# PSU_Manager.net
KiCad netlist of a schematic drawn in Altium Designer
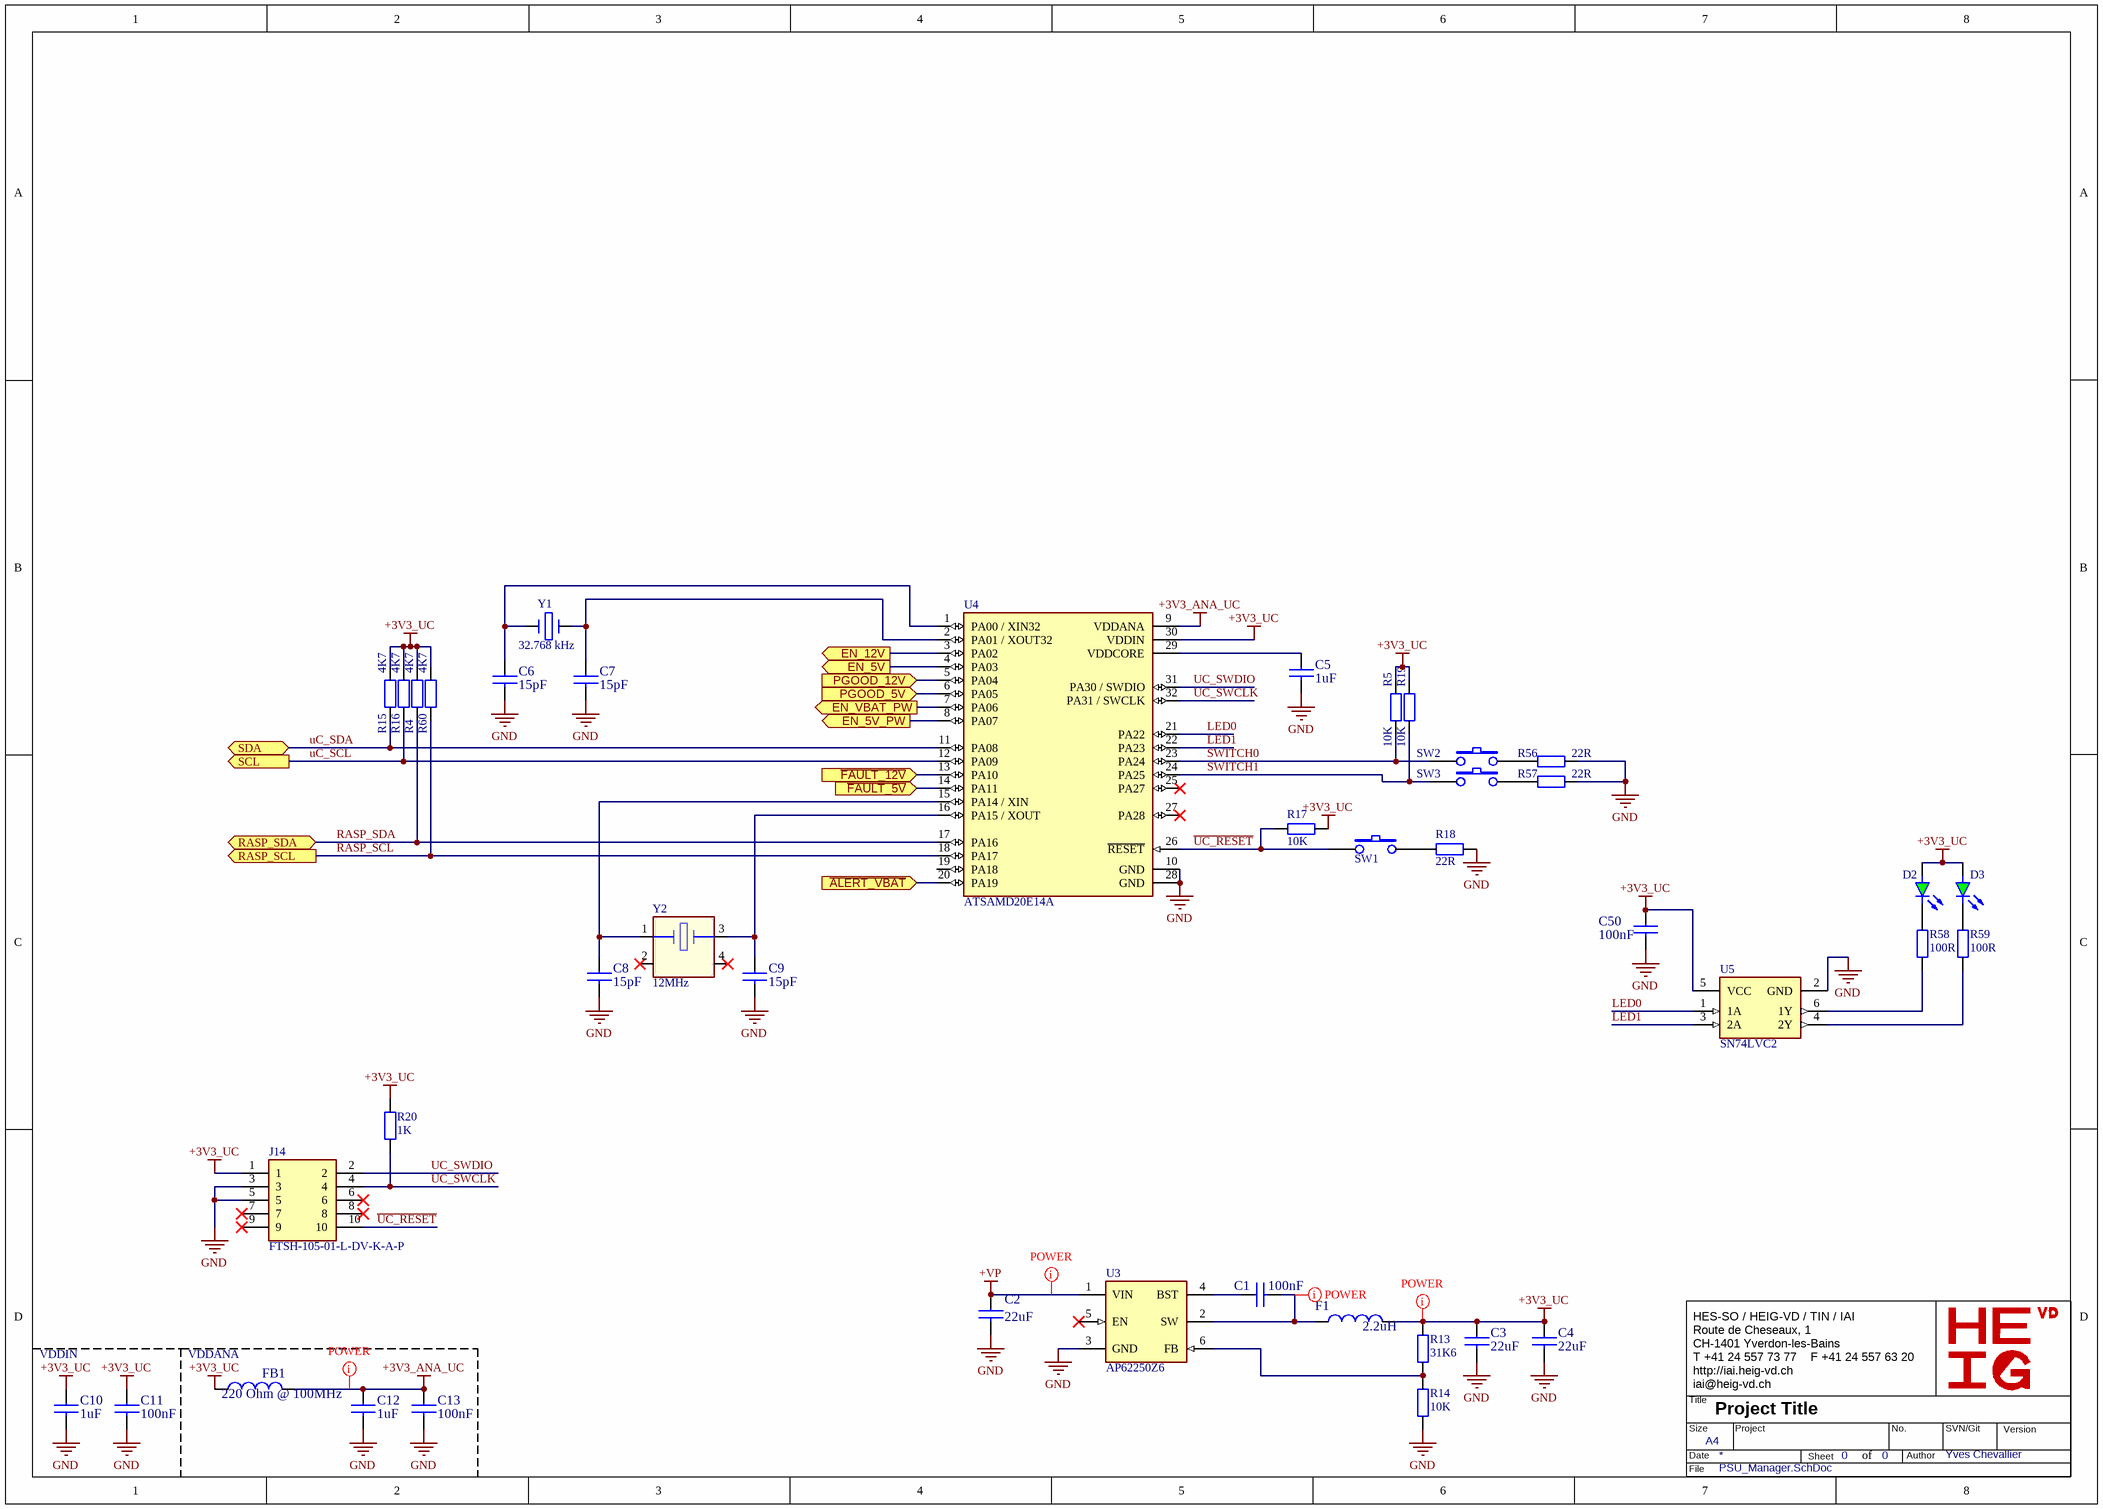
[diagram p0: PSU_Manager.SchDoc]

(export (version "E")
  (design (tool "Eeschema 10.0.6"))
  (components
    (comp (ref "C1")
      (value "100nF")
      (footprint "SM/C_0603")
      (description "CAP CER 0.1UF 16V X7R 0603")
      (fields (field (name "MANUFACTURER") "Samsung") (field (name "TOLERANCE") "10%"))
      (libsource (lib "Battery_PSU") (part "CAP CER 0.1UF 16V X7R 0603"))
    )
    (comp (ref "C2")
      (value "22uF")
      (footprint "SM/C_1210")
      (description "CAP CER 22UF 25V X5R 1210")
      (fields (field (name "MANUFACTURER") "Samsung") (field (name "VOLTAGE") "25V"))
      (libsource (lib "Battery_PSU") (part "CAP CER 22UF 25V X5R 1210"))
    )
    (comp (ref "C3")
      (value "22uF")
      (footprint "SM/C_1210")
      (description "CAP CER 22UF 25V X5R 1210")
      (fields (field (name "MANUFACTURER") "Samsung") (field (name "VOLTAGE") "25V"))
      (libsource (lib "Battery_PSU") (part "CAP CER 22UF 25V X5R 1210"))
    )
    (comp (ref "C4")
      (value "22uF")
      (footprint "SM/C_1210")
      (description "CAP CER 22UF 25V X5R 1210")
      (fields (field (name "MANUFACTURER") "Samsung") (field (name "VOLTAGE") "25V"))
      (libsource (lib "Battery_PSU") (part "CAP CER 22UF 25V X5R 1210"))
    )
    (comp (ref "C5")
      (value "1uF")
      (footprint "SM/C_0603")
      (description "CAP CER 1UF 10V X7R 0603")
      (fields (field (name "MANUFACTURER") "Samsung") (field (name "TOLERANCE") "10%"))
      (libsource (lib "Battery_PSU") (part "CAP CER 1UF 10V X7R 0603"))
    )
    (comp (ref "C6")
      (value "15pF")
      (footprint "SM/C_0603")
      (description "CAP CER 15PF 50V C0G/NP0 0603")
      (fields (field (name "MANUFACTURER") "AVX") (field (name "TOLERANCE") "5%"))
      (libsource (lib "Battery_PSU") (part "CAP CER 15PF 50V C0G/NP0 0603"))
    )
    (comp (ref "C7")
      (value "15pF")
      (footprint "SM/C_0603")
      (description "CAP CER 15PF 50V C0G/NP0 0603")
      (fields (field (name "MANUFACTURER") "AVX") (field (name "TOLERANCE") "5%"))
      (libsource (lib "Battery_PSU") (part "CAP CER 15PF 50V C0G/NP0 0603"))
    )
    (comp (ref "C8")
      (value "15pF")
      (footprint "SM/C_0603")
      (description "CAP CER 15PF 50V C0G/NP0 0603")
      (fields (field (name "MANUFACTURER") "AVX") (field (name "TOLERANCE") "5%"))
      (libsource (lib "Battery_PSU") (part "CAP CER 15PF 50V C0G/NP0 0603"))
    )
    (comp (ref "C9")
      (value "15pF")
      (footprint "SM/C_0603")
      (description "CAP CER 15PF 50V C0G/NP0 0603")
      (fields (field (name "MANUFACTURER") "AVX") (field (name "TOLERANCE") "5%"))
      (libsource (lib "Battery_PSU") (part "CAP CER 15PF 50V C0G/NP0 0603"))
    )
    (comp (ref "C10")
      (value "1uF")
      (footprint "SM/C_0603")
      (description "CAP CER 1UF 10V X7R 0603")
      (fields (field (name "MANUFACTURER") "Samsung") (field (name "TOLERANCE") "10%"))
      (libsource (lib "Battery_PSU") (part "CAP CER 1UF 10V X7R 0603"))
    )
    (comp (ref "C11")
      (value "100nF")
      (footprint "SM/C_0603")
      (description "CAP CER 0.1UF 16V X7R 0603")
      (fields (field (name "MANUFACTURER") "Samsung") (field (name "TOLERANCE") "10%"))
      (libsource (lib "Battery_PSU") (part "CAP CER 0.1UF 16V X7R 0603"))
    )
    (comp (ref "C12")
      (value "1uF")
      (footprint "SM/C_0603")
      (description "CAP CER 1UF 10V X7R 0603")
      (fields (field (name "MANUFACTURER") "Samsung") (field (name "TOLERANCE") "10%"))
      (libsource (lib "Battery_PSU") (part "CAP CER 1UF 10V X7R 0603"))
    )
    (comp (ref "C13")
      (value "100nF")
      (footprint "SM/C_0603")
      (description "CAP CER 0.1UF 16V X7R 0603")
      (fields (field (name "MANUFACTURER") "Samsung") (field (name "TOLERANCE") "10%"))
      (libsource (lib "Battery_PSU") (part "CAP CER 0.1UF 16V X7R 0603"))
    )
    (comp (ref "C50")
      (value "100nF")
      (footprint "SM/C_0603")
      (description "CAP CER 0.1UF 16V X7R 0603")
      (fields (field (name "MANUFACTURER") "Samsung") (field (name "TOLERANCE") "10%"))
      (libsource (lib "Battery_PSU") (part "CAP CER 0.1UF 16V X7R 0603"))
    )
    (comp (ref "D2")
      (value "Green")
      (footprint "WL-SMCW_0603 - Green")
      (description "LED GREEN CLEAR 0603 SMD")
      (fields (field (name "MANUFACTURER") "Würth Elektronik"))
      (libsource (lib "Battery_PSU") (part "LED GREEN CLEAR 0603 SMD"))
    )
    (comp (ref "D3")
      (value "Green")
      (footprint "WL-SMCW_0603 - Green")
      (description "LED GREEN CLEAR 0603 SMD")
      (fields (field (name "MANUFACTURER") "Würth Elektronik"))
      (libsource (lib "Battery_PSU") (part "LED GREEN CLEAR 0603 SMD"))
    )
    (comp (ref "F1")
      (value "2.2uH")
      (description "FIXED IND 2.2UH 4.7A 28.6MOHM SMD")
      (fields (field (name "MANUFACTURER") "TDK"))
      (libsource (lib "Battery_PSU") (part "FIXED IND 2.2UH 4.7A 28.6MOHM SMD"))
    )
    (comp (ref "FB1")
      (value "220 Ohm @ 100MHz")
      (description "FERRITE BEAD 220 OHM 0603 1LN")
      (fields (field (name "MANUFACTURER") "Murata"))
      (libsource (lib "Battery_PSU") (part "FERRITE 220 Ohms 0603"))
    )
    (comp (ref "J14")
      (value "FTSH-105-01-L-DV-K-A-P")
      (footprint "FTSH-105-XX-YYY-DV-K-A-P-TR")
      (description "CONN HEADER SMD 10POS 1.27MM")
      (fields (field (name "MANUFACTURER") "Samtec"))
      (libsource (lib "Battery_PSU") (part "CONN HEADER SMD 10POS 1.27MM"))
    )
    (comp (ref "R4")
      (value "4K7")
      (footprint "SM/R_0603")
      (description "RES SMD 4.7K OHM 1% 1/10W 0603")
      (fields (field (name "MANUFACTURER") "Yageo") (field (name "POWER") "100mW"))
      (libsource (lib "Battery_PSU") (part "RES SMD 4.7K OHM 1% 1/10W 0603"))
    )
    (comp (ref "R5")
      (value "10K")
      (footprint "SM/R_0603")
      (description "Résistance 0603 100mW 1% 10K")
      (fields (field (name "MANUFACTURER") "Yageo") (field (name "POWER") "100mW"))
      (libsource (lib "Battery_PSU") (part "RES SMD 10K OHM 1% 1/10W 0603"))
    )
    (comp (ref "R13")
      (value "31K6")
      (footprint "SM/R_0603")
      (description "RES SMD 31.6K OHM 1% 1/10W 0603")
      (fields (field (name "MANUFACTURER") "Yageo") (field (name "POWER") "100mW"))
      (libsource (lib "Battery_PSU") (part "RES SMD 31.6K OHM 1% 1/10W 0603"))
    )
    (comp (ref "R14")
      (value "10K")
      (footprint "SM/R_0603")
      (description "Résistance 0603 100mW 1% 10K")
      (fields (field (name "MANUFACTURER") "Yageo") (field (name "POWER") "100mW"))
      (libsource (lib "Battery_PSU") (part "RES SMD 10K OHM 1% 1/10W 0603"))
    )
    (comp (ref "R15")
      (value "4K7")
      (footprint "SM/R_0603")
      (description "RES SMD 4.7K OHM 1% 1/10W 0603")
      (fields (field (name "MANUFACTURER") "Yageo") (field (name "POWER") "100mW"))
      (libsource (lib "Battery_PSU") (part "RES SMD 4.7K OHM 1% 1/10W 0603"))
    )
    (comp (ref "R16")
      (value "4K7")
      (footprint "SM/R_0603")
      (description "RES SMD 4.7K OHM 1% 1/10W 0603")
      (fields (field (name "MANUFACTURER") "Yageo") (field (name "POWER") "100mW"))
      (libsource (lib "Battery_PSU") (part "RES SMD 4.7K OHM 1% 1/10W 0603"))
    )
    (comp (ref "R17")
      (value "10K")
      (footprint "SM/R_0603")
      (description "Résistance 0603 100mW 1% 10K")
      (fields (field (name "MANUFACTURER") "Yageo") (field (name "POWER") "100mW"))
      (libsource (lib "Battery_PSU") (part "RES SMD 10K OHM 1% 1/10W 0603"))
    )
    (comp (ref "R18")
      (value "22R")
      (footprint "SM/R_0603")
      (description "RES SMD 22 OHM 1% 1/10W 0603")
      (fields (field (name "MANUFACTURER") "Yageo") (field (name "POWER") "100mW"))
      (libsource (lib "Battery_PSU") (part "RES SMD 22 OHM 1% 1/10W 0603"))
    )
    (comp (ref "R19")
      (value "10K")
      (footprint "SM/R_0603")
      (description "Résistance 0603 100mW 1% 10K")
      (fields (field (name "MANUFACTURER") "Yageo") (field (name "POWER") "100mW"))
      (libsource (lib "Battery_PSU") (part "RES SMD 10K OHM 1% 1/10W 0603"))
    )
    (comp (ref "R20")
      (value "1K")
      (footprint "SM/R_0603")
      (description "RES SMD 1K OHM 1% 1/10W 0603")
      (fields (field (name "MANUFACTURER") "Yageo") (field (name "POWER") "100mW"))
      (libsource (lib "Battery_PSU") (part "RES SMD 1K OHM 1% 1/10W 0603"))
    )
    (comp (ref "R56")
      (value "22R")
      (footprint "SM/R_0603")
      (description "RES SMD 22 OHM 1% 1/10W 0603")
      (fields (field (name "MANUFACTURER") "Yageo") (field (name "POWER") "100mW"))
      (libsource (lib "Battery_PSU") (part "RES SMD 22 OHM 1% 1/10W 0603"))
    )
    (comp (ref "R57")
      (value "22R")
      (footprint "SM/R_0603")
      (description "RES SMD 22 OHM 1% 1/10W 0603")
      (fields (field (name "MANUFACTURER") "Yageo") (field (name "POWER") "100mW"))
      (libsource (lib "Battery_PSU") (part "RES SMD 22 OHM 1% 1/10W 0603"))
    )
    (comp (ref "R58")
      (value "100R")
      (footprint "SM/R_0603")
      (description "RES 100 OHM 1% 1/10W 0603")
      (fields (field (name "MANUFACTURER") "Yageo") (field (name "POWER") "100mW"))
      (libsource (lib "Battery_PSU") (part "RES 100 OHM 1% 1/10W 0603"))
    )
    (comp (ref "R59")
      (value "100R")
      (footprint "SM/R_0603")
      (description "RES 100 OHM 1% 1/10W 0603")
      (fields (field (name "MANUFACTURER") "Yageo") (field (name "POWER") "100mW"))
      (libsource (lib "Battery_PSU") (part "RES 100 OHM 1% 1/10W 0603"))
    )
    (comp (ref "R60")
      (value "4K7")
      (footprint "SM/R_0603")
      (description "RES SMD 4.7K OHM 1% 1/10W 0603")
      (fields (field (name "MANUFACTURER") "Yageo") (field (name "POWER") "100mW"))
      (libsource (lib "Battery_PSU") (part "RES SMD 4.7K OHM 1% 1/10W 0603"))
    )
    (comp (ref "SW1")
      (value "SW_PUSHBUTTON")
      (footprint "Omron_SWITCH_B3U-1000P")
      (description "Tactile Switch SPST-NO Top Actuated SMD")
      (fields (field (name "MANUFACTURER") "Omron Electronics") (field (name "VOLTAGE") "12V"))
      (libsource (lib "Battery_PSU") (part "SWITCH TACTILE SPST-NO 0.05A 12V"))
    )
    (comp (ref "SW2")
      (value "SW_PUSHBUTTON")
      (footprint "Omron_SWITCH_B3U-1000P")
      (description "Tactile Switch SPST-NO Top Actuated SMD")
      (fields (field (name "MANUFACTURER") "Omron Electronics") (field (name "VOLTAGE") "12V"))
      (libsource (lib "Battery_PSU") (part "SWITCH TACTILE SPST-NO 0.05A 12V"))
    )
    (comp (ref "SW3")
      (value "SW_PUSHBUTTON")
      (footprint "Omron_SWITCH_B3U-1000P")
      (description "Tactile Switch SPST-NO Top Actuated SMD")
      (fields (field (name "MANUFACTURER") "Omron Electronics") (field (name "VOLTAGE") "12V"))
      (libsource (lib "Battery_PSU") (part "SWITCH TACTILE SPST-NO 0.05A 12V"))
    )
    (comp (ref "U3")
      (value "AP62250Z6")
      (footprint "SOT563-6")
      (description "DCDC CONV BUCK 3A SOT563")
      (fields (field (name "MANUFACTURER") "Diodes Incorporated"))
      (libsource (lib "Battery_PSU") (part "AP62250Z6-7"))
    )
    (comp (ref "U4")
      (value "ATSAMD20E14A")
      (footprint "VFQFN-32_(32-Lead LFCSP_VQ)")
      (description "IC MCU 32BIT 16KB FLASH 32QFN")
      (fields (field (name "MANUFACTURER") "Microchip"))
      (libsource (lib "Battery_PSU") (part "IC MCU 32BIT 16KB FLASH 32QFN"))
    )
    (comp (ref "U5")
      (value "SN74LVC2")
      (footprint "SOT23-6")
      (description "IC INVERTER 2CH 2-INP SOT23-6")
      (fields (field (name "MANUFACTURER") "Texas Instruments"))
      (libsource (lib "Battery_PSU") (part "SN74LVC2GU04DBVR"))
    )
    (comp (ref "Y1")
      (value "32.768 kHz")
      (footprint "ABRACON_CRYSTAL_ABS06 SERIES")
      (description "CRYSTAL 32.7680KHZ 12.5PF SMD")
      (fields (field (name "MANUFACTURER") "Abracon LLC"))
      (libsource (lib "Battery_PSU") (part "CRYSTAL 32.7680KHZ 12.5PF SMD"))
    )
    (comp (ref "Y2")
      (value "12MHz")
      (footprint "ABRACON_CRYSTAL_ABM10AIG SERIES")
      (description "CRYSTAL 12.0000MHZ 10PF SMD")
      (fields (field (name "MANUFACTURER") "Abracon LLC"))
      (libsource (lib "Battery_PSU") (part "CRYSTAL 12.0000MHZ 10PF SMD"))
    )
  )
  (nets
    (net (code "1") (name "+3V3_ANA_UC") (class "Default")
      (node (ref "C12") (pin "1") (pinfunction "1_1") (pintype "passive"))
      (node (ref "C13") (pin "1") (pinfunction "1_1") (pintype "passive"))
      (node (ref "FB1") (pin "2") (pinfunction "2_2") (pintype "passive"))
      (node (ref "U4") (pin "9") (pinfunction "VDDANA_9") (pintype "power_in"))
    )
    (net (code "2") (name "+3V3_UC") (class "Default")
      (node (ref "C10") (pin "1") (pinfunction "1_1") (pintype "passive"))
      (node (ref "C11") (pin "1") (pinfunction "1_1") (pintype "passive"))
      (node (ref "C3") (pin "1") (pinfunction "1_1") (pintype "passive"))
      (node (ref "C4") (pin "1") (pinfunction "1_1") (pintype "passive"))
      (node (ref "C50") (pin "1") (pinfunction "1_1") (pintype "passive"))
      (node (ref "D2") (pin "2") (pinfunction "A_2") (pintype "passive"))
      (node (ref "D3") (pin "2") (pinfunction "A_2") (pintype "passive"))
      (node (ref "F1") (pin "2") (pinfunction "2_2") (pintype "passive"))
      (node (ref "FB1") (pin "1") (pinfunction "1_1") (pintype "passive"))
      (node (ref "J14") (pin "1") (pinfunction "1_1") (pintype "passive"))
      (node (ref "R13") (pin "1") (pinfunction "1_1") (pintype "passive"))
      (node (ref "R15") (pin "1") (pinfunction "1_1") (pintype "passive"))
      (node (ref "R16") (pin "1") (pinfunction "1_1") (pintype "passive"))
      (node (ref "R17") (pin "2") (pinfunction "2_2") (pintype "passive"))
      (node (ref "R19") (pin "2") (pinfunction "2_2") (pintype "passive"))
      (node (ref "R20") (pin "1") (pinfunction "1_1") (pintype "passive"))
      (node (ref "R4") (pin "1") (pinfunction "1_1") (pintype "passive"))
      (node (ref "R5") (pin "2") (pinfunction "2_2") (pintype "passive"))
      (node (ref "R60") (pin "1") (pinfunction "1_1") (pintype "passive"))
      (node (ref "U4") (pin "30") (pinfunction "VDDIN_30") (pintype "power_in"))
      (node (ref "U5") (pin "5") (pinfunction "VCC_5") (pintype "power_in"))
    )
    (net (code "3") (name "+VP") (class "Default")
      (node (ref "C2") (pin "1") (pinfunction "1_1") (pintype "passive"))
      (node (ref "U3") (pin "1") (pinfunction "VIN_1") (pintype "power_in"))
    )
    (net (code "4") (name "/ALERT_VBAT") (class "Default")
      (node (ref "U4") (pin "20") (pinfunction "PA19_20") (pintype "bidirectional"))
    )
    (net (code "5") (name "/EN_5V") (class "Default")
      (node (ref "U4") (pin "4") (pinfunction "PA03_4") (pintype "bidirectional"))
    )
    (net (code "6") (name "/EN_5V_PW") (class "Default")
      (node (ref "U4") (pin "8") (pinfunction "PA07_8") (pintype "bidirectional"))
    )
    (net (code "7") (name "/EN_12V") (class "Default")
      (node (ref "U4") (pin "3") (pinfunction "PA02_3") (pintype "bidirectional"))
    )
    (net (code "8") (name "/EN_VBAT_PW") (class "Default")
      (node (ref "U4") (pin "7") (pinfunction "PA06_7") (pintype "bidirectional"))
    )
    (net (code "9") (name "/FAULT_5V") (class "Default")
      (node (ref "U4") (pin "14") (pinfunction "PA11_14") (pintype "bidirectional"))
    )
    (net (code "10") (name "/FAULT_12V") (class "Default")
      (node (ref "U4") (pin "13") (pinfunction "PA10_13") (pintype "bidirectional"))
    )
    (net (code "11") (name "/LED0") (class "Default")
      (node (ref "U4") (pin "21") (pinfunction "PA22_21") (pintype "bidirectional"))
      (node (ref "U5") (pin "1") (pinfunction "1A_1") (pintype "input"))
    )
    (net (code "12") (name "/LED1") (class "Default")
      (node (ref "U4") (pin "22") (pinfunction "PA23_22") (pintype "bidirectional"))
      (node (ref "U5") (pin "3") (pinfunction "2A_3") (pintype "input"))
    )
    (net (code "13") (name "/PGOOD_5V") (class "Default")
      (node (ref "U4") (pin "6") (pinfunction "PA05_6") (pintype "bidirectional"))
    )
    (net (code "14") (name "/PGOOD_12V") (class "Default")
      (node (ref "U4") (pin "5") (pinfunction "PA04_5") (pintype "bidirectional"))
    )
    (net (code "15") (name "/RASP_SCL") (class "Default")
      (node (ref "R60") (pin "2") (pinfunction "2_2") (pintype "passive"))
      (node (ref "U4") (pin "18") (pinfunction "PA17_18") (pintype "bidirectional"))
    )
    (net (code "16") (name "/RASP_SDA") (class "Default")
      (node (ref "R4") (pin "2") (pinfunction "2_2") (pintype "passive"))
      (node (ref "U4") (pin "17") (pinfunction "PA16_17") (pintype "bidirectional"))
    )
    (net (code "17") (name "/SWITCH0") (class "Default")
      (node (ref "R5") (pin "1") (pinfunction "1_1") (pintype "passive"))
      (node (ref "SW2") (pin "1") (pinfunction "1_1") (pintype "passive"))
      (node (ref "U4") (pin "23") (pinfunction "PA24_23") (pintype "bidirectional"))
    )
    (net (code "18") (name "/SWITCH1") (class "Default")
      (node (ref "R19") (pin "1") (pinfunction "1_1") (pintype "passive"))
      (node (ref "SW3") (pin "1") (pinfunction "1_1") (pintype "passive"))
      (node (ref "U4") (pin "24") (pinfunction "PA25_24") (pintype "bidirectional"))
    )
    (net (code "19") (name "/UC_RESET") (class "Default")
      (node (ref "J14") (pin "10") (pinfunction "10_10") (pintype "passive"))
      (node (ref "R17") (pin "1") (pinfunction "1_1") (pintype "passive"))
      (node (ref "SW1") (pin "1") (pinfunction "1_1") (pintype "passive"))
      (node (ref "U4") (pin "26") (pinfunction "RESET_26") (pintype "input"))
    )
    (net (code "20") (name "/UC_SWCLK") (class "Default")
      (node (ref "J14") (pin "4") (pinfunction "4_4") (pintype "passive"))
      (node (ref "R20") (pin "2") (pinfunction "2_2") (pintype "passive"))
      (node (ref "U4") (pin "32") (pinfunction "PA31_/_SWCLK_32") (pintype "bidirectional"))
    )
    (net (code "21") (name "/UC_SWDIO") (class "Default")
      (node (ref "J14") (pin "2") (pinfunction "2_2") (pintype "passive"))
      (node (ref "U4") (pin "31") (pinfunction "PA30_/_SWDIO_31") (pintype "bidirectional"))
    )
    (net (code "22") (name "/uC_SCL") (class "Default")
      (node (ref "R16") (pin "2") (pinfunction "2_2") (pintype "passive"))
      (node (ref "U4") (pin "12") (pinfunction "PA09_12") (pintype "bidirectional"))
    )
    (net (code "23") (name "/uC_SDA") (class "Default")
      (node (ref "R15") (pin "2") (pinfunction "2_2") (pintype "passive"))
      (node (ref "U4") (pin "11") (pinfunction "PA08_11") (pintype "bidirectional"))
    )
    (net (code "24") (name "GND") (class "Default")
      (node (ref "C10") (pin "2") (pinfunction "2_2") (pintype "passive"))
      (node (ref "C11") (pin "2") (pinfunction "2_2") (pintype "passive"))
      (node (ref "C12") (pin "2") (pinfunction "2_2") (pintype "passive"))
      (node (ref "C13") (pin "2") (pinfunction "2_2") (pintype "passive"))
      (node (ref "C2") (pin "2") (pinfunction "2_2") (pintype "passive"))
      (node (ref "C3") (pin "2") (pinfunction "2_2") (pintype "passive"))
      (node (ref "C4") (pin "2") (pinfunction "2_2") (pintype "passive"))
      (node (ref "C5") (pin "2") (pinfunction "2_2") (pintype "passive"))
      (node (ref "C50") (pin "2") (pinfunction "2_2") (pintype "passive"))
      (node (ref "C6") (pin "2") (pinfunction "2_2") (pintype "passive"))
      (node (ref "C7") (pin "2") (pinfunction "2_2") (pintype "passive"))
      (node (ref "C8") (pin "2") (pinfunction "2_2") (pintype "passive"))
      (node (ref "C9") (pin "2") (pinfunction "2_2") (pintype "passive"))
      (node (ref "J14") (pin "3") (pinfunction "3_3") (pintype "passive"))
      (node (ref "J14") (pin "5") (pinfunction "5_5") (pintype "passive"))
      (node (ref "R14") (pin "2") (pinfunction "2_2") (pintype "passive"))
      (node (ref "R18") (pin "2") (pinfunction "2_2") (pintype "passive"))
      (node (ref "R56") (pin "2") (pinfunction "2_2") (pintype "passive"))
      (node (ref "R57") (pin "2") (pinfunction "2_2") (pintype "passive"))
      (node (ref "U3") (pin "3") (pinfunction "GND_3") (pintype "power_in"))
      (node (ref "U4") (pin "10") (pinfunction "GND_10") (pintype "power_in"))
      (node (ref "U4") (pin "28") (pinfunction "GND_28") (pintype "power_in"))
      (node (ref "U5") (pin "2") (pinfunction "GND_2") (pintype "power_in"))
    )
    (net (code "25") (name "Net-(D2-C)") (class "Default")
      (node (ref "D2") (pin "1") (pinfunction "C_1") (pintype "passive"))
      (node (ref "R58") (pin "1") (pinfunction "1_1") (pintype "passive"))
    )
    (net (code "26") (name "Net-(D3-C)") (class "Default")
      (node (ref "D3") (pin "1") (pinfunction "C_1") (pintype "passive"))
      (node (ref "R59") (pin "1") (pinfunction "1_1") (pintype "passive"))
    )
    (net (code "27") (name "Net-(R18-Pad1)") (class "Default")
      (node (ref "R18") (pin "1") (pinfunction "1_1") (pintype "passive"))
      (node (ref "SW1") (pin "2") (pinfunction "2_2") (pintype "passive"))
    )
    (net (code "28") (name "Net-(R56-Pad1)") (class "Default")
      (node (ref "R56") (pin "1") (pinfunction "1_1") (pintype "passive"))
      (node (ref "SW2") (pin "2") (pinfunction "2_2") (pintype "passive"))
    )
    (net (code "29") (name "Net-(R57-Pad1)") (class "Default")
      (node (ref "R57") (pin "1") (pinfunction "1_1") (pintype "passive"))
      (node (ref "SW3") (pin "2") (pinfunction "2_2") (pintype "passive"))
    )
    (net (code "30") (name "Net-(U3-BST)") (class "Default")
      (node (ref "C1") (pin "1") (pinfunction "1_1") (pintype "passive"))
      (node (ref "U3") (pin "4") (pinfunction "BST_4") (pintype "passive"))
    )
    (net (code "31") (name "Net-(U3-FB)") (class "Default")
      (node (ref "R13") (pin "2") (pinfunction "2_2") (pintype "passive"))
      (node (ref "R14") (pin "1") (pinfunction "1_1") (pintype "passive"))
      (node (ref "U3") (pin "6") (pinfunction "FB_6") (pintype "input"))
    )
    (net (code "32") (name "Net-(U3-SW)") (class "Default")
      (node (ref "C1") (pin "2") (pinfunction "2_2") (pintype "passive"))
      (node (ref "F1") (pin "1") (pinfunction "1_1") (pintype "passive"))
      (node (ref "U3") (pin "2") (pinfunction "SW_2") (pintype "power_in"))
    )
    (net (code "33") (name "Net-(U4-PA00_{slash}_XIN32)") (class "Default")
      (node (ref "C6") (pin "1") (pinfunction "1_1") (pintype "passive"))
      (node (ref "U4") (pin "1") (pinfunction "PA00_/_XIN32_1") (pintype "bidirectional"))
      (node (ref "Y1") (pin "1") (pintype "passive"))
    )
    (net (code "34") (name "Net-(U4-PA01_{slash}_XOUT32)") (class "Default")
      (node (ref "C7") (pin "1") (pinfunction "1_1") (pintype "passive"))
      (node (ref "U4") (pin "2") (pinfunction "PA01_/_XOUT32_2") (pintype "bidirectional"))
      (node (ref "Y1") (pin "2") (pintype "passive"))
    )
    (net (code "35") (name "Net-(U4-PA14_{slash}_XIN)") (class "Default")
      (node (ref "C8") (pin "1") (pinfunction "1_1") (pintype "passive"))
      (node (ref "U4") (pin "15") (pinfunction "PA14_/_XIN_15") (pintype "bidirectional"))
      (node (ref "Y2") (pin "1") (pintype "passive"))
    )
    (net (code "36") (name "Net-(U4-PA15_{slash}_XOUT)") (class "Default")
      (node (ref "C9") (pin "1") (pinfunction "1_1") (pintype "passive"))
      (node (ref "U4") (pin "16") (pinfunction "PA15_/_XOUT_16") (pintype "bidirectional"))
      (node (ref "Y2") (pin "3") (pintype "passive"))
    )
    (net (code "37") (name "Net-(U4-VDDCORE)") (class "Default")
      (node (ref "C5") (pin "1") (pinfunction "1_1") (pintype "passive"))
      (node (ref "U4") (pin "29") (pinfunction "VDDCORE_29") (pintype "power_in"))
    )
    (net (code "38") (name "Net-(U5-1Y)") (class "Default")
      (node (ref "R58") (pin "2") (pinfunction "2_2") (pintype "passive"))
      (node (ref "U5") (pin "6") (pinfunction "1Y_6") (pintype "output"))
    )
    (net (code "39") (name "Net-(U5-2Y)") (class "Default")
      (node (ref "R59") (pin "2") (pinfunction "2_2") (pintype "passive"))
      (node (ref "U5") (pin "4") (pinfunction "2Y_4") (pintype "output"))
    )
    (net (code "40") (name "unconnected-(J14-Pad6)") (class "Default")
      (node (ref "J14") (pin "6") (pinfunction "6_6") (pintype "passive+no_connect"))
    )
    (net (code "41") (name "unconnected-(J14-Pad7)") (class "Default")
      (node (ref "J14") (pin "7") (pinfunction "7_7") (pintype "passive+no_connect"))
    )
    (net (code "42") (name "unconnected-(J14-Pad8)") (class "Default")
      (node (ref "J14") (pin "8") (pinfunction "8_8") (pintype "passive+no_connect"))
    )
    (net (code "43") (name "unconnected-(J14-Pad9)") (class "Default")
      (node (ref "J14") (pin "9") (pinfunction "9_9") (pintype "passive+no_connect"))
    )
    (net (code "44") (name "unconnected-(U3-EN-Pad5)") (class "Default")
      (node (ref "U3") (pin "5") (pinfunction "EN_5") (pintype "input+no_connect"))
    )
    (net (code "45") (name "unconnected-(U4-PA18-Pad19)") (class "Default")
      (node (ref "U4") (pin "19") (pinfunction "PA18_19") (pintype "bidirectional"))
    )
    (net (code "46") (name "unconnected-(U4-PA27-Pad25)") (class "Default")
      (node (ref "U4") (pin "25") (pinfunction "PA27_25") (pintype "bidirectional+no_connect"))
    )
    (net (code "47") (name "unconnected-(U4-PA28-Pad27)") (class "Default")
      (node (ref "U4") (pin "27") (pinfunction "PA28_27") (pintype "bidirectional+no_connect"))
    )
    (net (code "48") (name "unconnected-(Y2-GND-Pad2)") (class "Default")
      (node (ref "Y2") (pin "2") (pinfunction "GND_2") (pintype "power_in+no_connect"))
    )
    (net (code "49") (name "unconnected-(Y2-GND-Pad4)") (class "Default")
      (node (ref "Y2") (pin "4") (pinfunction "GND_4") (pintype "power_in+no_connect"))
    )
  )
)
